# waveshaper.net
KiCad netlist of a schematic drawn in EAGLE
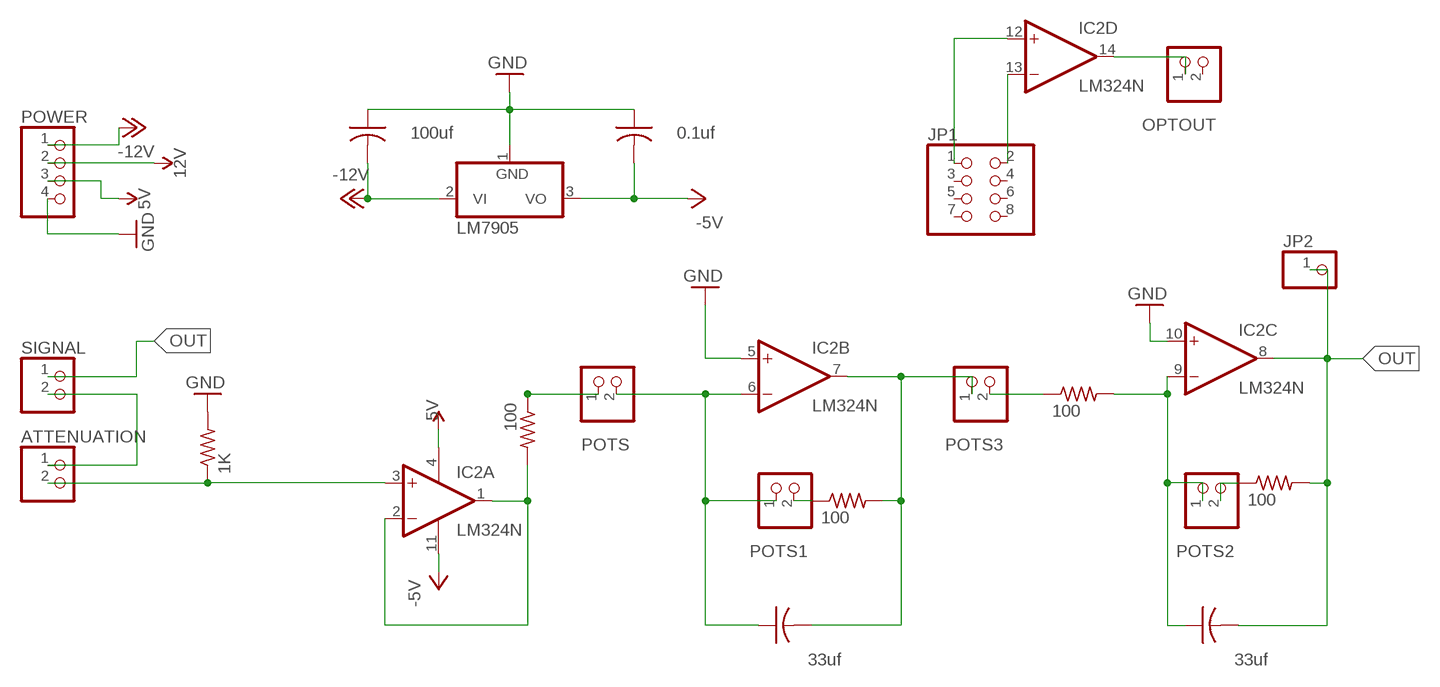
[diagram p0: schematic, sheet 1]

(export (version "E")
  (design (tool "Eeschema 10.0.6"))
  (components
    (comp (ref "ATTENUATION")
      (value "PINHD-1X2")
      (footprint "eagle-import:1X02")
      (libsource (lib "eagle-import") (part "PINHD-1X2"))
    )
    (comp (ref "C1")
      (value "100uf")
      (footprint "eagle-import:C025-024X044")
      (libsource (lib "eagle-import") (part "C-US025-024X044"))
    )
    (comp (ref "C2")
      (value "0.1uf")
      (footprint "eagle-import:C025-024X044")
      (libsource (lib "eagle-import") (part "C-US025-024X044"))
    )
    (comp (ref "C3")
      (value "33uf")
      (footprint "eagle-import:C025-024X044")
      (libsource (lib "eagle-import") (part "C-US025-024X044"))
    )
    (comp (ref "C4")
      (value "33uf")
      (footprint "eagle-import:C025-024X044")
      (libsource (lib "eagle-import") (part "C-US025-024X044"))
    )
    (comp (ref "IC2")
      (value "LM324N")
      (footprint "eagle-import:DIL14")
      (libsource (lib "eagle-import") (part "LM324N"))
    )
    (comp (ref "JP1")
      (value "PINHD-2X4")
      (footprint "eagle-import:2X04")
      (libsource (lib "eagle-import") (part "PINHD-2X4"))
    )
    (comp (ref "JP2")
      (value "PINHD-1X1")
      (footprint "eagle-import:1X01")
      (libsource (lib "eagle-import") (part "PINHD-1X1"))
    )
    (comp (ref "LM7905")
      (value "7905T")
      (footprint "eagle-import:TO220H")
      (libsource (lib "eagle-import") (part "79T05"))
    )
    (comp (ref "OPTOUT")
      (value "PINHD-1X2")
      (footprint "eagle-import:1X02")
      (libsource (lib "eagle-import") (part "PINHD-1X2"))
    )
    (comp (ref "POTS")
      (value "PINHD-1X2")
      (footprint "eagle-import:1X02")
      (libsource (lib "eagle-import") (part "PINHD-1X2"))
    )
    (comp (ref "POTS1")
      (value "PINHD-1X2")
      (footprint "eagle-import:1X02")
      (libsource (lib "eagle-import") (part "PINHD-1X2"))
    )
    (comp (ref "POTS2")
      (value "PINHD-1X2")
      (footprint "eagle-import:1X02")
      (libsource (lib "eagle-import") (part "PINHD-1X2"))
    )
    (comp (ref "POTS3")
      (value "PINHD-1X2")
      (footprint "eagle-import:1X02")
      (libsource (lib "eagle-import") (part "PINHD-1X2"))
    )
    (comp (ref "POWER")
      (value "PINHD-1X4")
      (footprint "eagle-import:1X04")
      (libsource (lib "eagle-import") (part "PINHD-1X4"))
    )
    (comp (ref "R1")
      (value "1K")
      (footprint "eagle-import:0207_12")
      (libsource (lib "eagle-import") (part "R-US_0207/12"))
    )
    (comp (ref "R2")
      (value "100")
      (footprint "eagle-import:0207_12")
      (libsource (lib "eagle-import") (part "R-US_0207/12"))
    )
    (comp (ref "R3")
      (value "100")
      (footprint "eagle-import:0207_12")
      (libsource (lib "eagle-import") (part "R-US_0207/12"))
    )
    (comp (ref "R4")
      (value "100")
      (footprint "eagle-import:0207_12")
      (libsource (lib "eagle-import") (part "R-US_0207/12"))
    )
    (comp (ref "R5")
      (value "100")
      (footprint "eagle-import:0207_12")
      (libsource (lib "eagle-import") (part "R-US_0207/12"))
    )
    (comp (ref "SIGNAL")
      (value "PINHD-1X2")
      (footprint "eagle-import:1X02")
      (libsource (lib "eagle-import") (part "PINHD-1X2"))
    )
  )
  (nets
    (net (code "1") (name "-5V") (class "Default")
      (node (ref "C2") (pin "2") (pinfunction "2_2") (pintype "passive"))
      (node (ref "IC2") (pin "11") (pinfunction "V-_11") (pintype "power_in"))
      (node (ref "LM7905") (pin "3") (pinfunction "VO_3") (pintype "passive"))
    )
    (net (code "2") (name "-12V") (class "Default")
      (node (ref "C1") (pin "2") (pinfunction "2_2") (pintype "passive"))
      (node (ref "LM7905") (pin "2") (pinfunction "VI_2") (pintype "input"))
      (node (ref "POWER") (pin "1") (pinfunction "1_1") (pintype "passive"))
    )
    (net (code "3") (name "5V") (class "Default")
      (node (ref "IC2") (pin "4") (pinfunction "V+_4") (pintype "power_in"))
      (node (ref "POWER") (pin "3") (pinfunction "3_3") (pintype "passive"))
    )
    (net (code "4") (name "12V") (class "Default")
      (node (ref "POWER") (pin "2") (pinfunction "2_2") (pintype "passive"))
    )
    (net (code "5") (name "GND") (class "Default")
      (node (ref "C1") (pin "1") (pinfunction "1_1") (pintype "passive"))
      (node (ref "C2") (pin "1") (pinfunction "1_1") (pintype "passive"))
      (node (ref "IC2") (pin "10") (pinfunction "+IN_10") (pintype "input"))
      (node (ref "IC2") (pin "5") (pinfunction "+IN_5") (pintype "input"))
      (node (ref "LM7905") (pin "1") (pinfunction "GND_1") (pintype "passive"))
      (node (ref "POWER") (pin "4") (pinfunction "4_4") (pintype "passive"))
      (node (ref "R1") (pin "2") (pinfunction "2_2") (pintype "passive"))
    )
    (net (code "6") (name "Net-(ATTENUATION-Pad1)") (class "Default")
      (node (ref "ATTENUATION") (pin "1") (pinfunction "1_1") (pintype "passive"))
      (node (ref "SIGNAL") (pin "2") (pinfunction "2_2") (pintype "passive"))
    )
    (net (code "7") (name "Net-(IC2A-+IN)") (class "Default")
      (node (ref "ATTENUATION") (pin "2") (pinfunction "2_2") (pintype "passive"))
      (node (ref "IC2") (pin "3") (pinfunction "+IN_3") (pintype "input"))
      (node (ref "R1") (pin "1") (pinfunction "1_1") (pintype "passive"))
    )
    (net (code "8") (name "Net-(IC2A--IN)") (class "Default")
      (node (ref "IC2") (pin "1") (pinfunction "OUT_1") (pintype "output"))
      (node (ref "IC2") (pin "2") (pinfunction "-IN_2") (pintype "input"))
      (node (ref "R2") (pin "2") (pinfunction "2_2") (pintype "passive"))
    )
    (net (code "9") (name "Net-(IC2B--IN)") (class "Default")
      (node (ref "C3") (pin "1") (pinfunction "1_1") (pintype "passive"))
      (node (ref "IC2") (pin "6") (pinfunction "-IN_6") (pintype "input"))
      (node (ref "POTS") (pin "2") (pinfunction "2_2") (pintype "passive"))
      (node (ref "POTS1") (pin "1") (pinfunction "1_1") (pintype "passive"))
    )
    (net (code "10") (name "Net-(IC2B-OUT)") (class "Default")
      (node (ref "C3") (pin "2") (pinfunction "2_2") (pintype "passive"))
      (node (ref "IC2") (pin "7") (pinfunction "OUT_7") (pintype "output"))
      (node (ref "POTS3") (pin "1") (pinfunction "1_1") (pintype "passive"))
      (node (ref "R3") (pin "2") (pinfunction "2_2") (pintype "passive"))
    )
    (net (code "11") (name "Net-(IC2C--IN)") (class "Default")
      (node (ref "C4") (pin "1") (pinfunction "1_1") (pintype "passive"))
      (node (ref "IC2") (pin "9") (pinfunction "-IN_9") (pintype "input"))
      (node (ref "POTS2") (pin "1") (pinfunction "1_1") (pintype "passive"))
      (node (ref "R5") (pin "2") (pinfunction "2_2") (pintype "passive"))
    )
    (net (code "12") (name "Net-(IC2D-+IN)") (class "Default")
      (node (ref "IC2") (pin "12") (pinfunction "+IN_12") (pintype "input"))
      (node (ref "JP1") (pin "1") (pinfunction "1_1") (pintype "passive"))
    )
    (net (code "13") (name "Net-(IC2D--IN)") (class "Default")
      (node (ref "IC2") (pin "13") (pinfunction "-IN_13") (pintype "input"))
      (node (ref "JP1") (pin "2") (pinfunction "2_2") (pintype "passive"))
    )
    (net (code "14") (name "Net-(IC2D-OUT)") (class "Default")
      (node (ref "IC2") (pin "14") (pinfunction "OUT_14") (pintype "output"))
      (node (ref "OPTOUT") (pin "1") (pinfunction "1_1") (pintype "passive"))
    )
    (net (code "15") (name "Net-(POTS-Pad1)") (class "Default")
      (node (ref "POTS") (pin "1") (pinfunction "1_1") (pintype "passive"))
      (node (ref "R2") (pin "1") (pinfunction "1_1") (pintype "passive"))
    )
    (net (code "16") (name "Net-(POTS1-Pad2)") (class "Default")
      (node (ref "POTS1") (pin "2") (pinfunction "2_2") (pintype "passive"))
      (node (ref "R3") (pin "1") (pinfunction "1_1") (pintype "passive"))
    )
    (net (code "17") (name "Net-(POTS2-Pad2)") (class "Default")
      (node (ref "POTS2") (pin "2") (pinfunction "2_2") (pintype "passive"))
      (node (ref "R4") (pin "1") (pinfunction "1_1") (pintype "passive"))
    )
    (net (code "18") (name "Net-(POTS3-Pad2)") (class "Default")
      (node (ref "POTS3") (pin "2") (pinfunction "2_2") (pintype "passive"))
      (node (ref "R5") (pin "1") (pinfunction "1_1") (pintype "passive"))
    )
    (net (code "19") (name "OUT") (class "Default")
      (node (ref "C4") (pin "2") (pinfunction "2_2") (pintype "passive"))
      (node (ref "IC2") (pin "8") (pinfunction "OUT_8") (pintype "output"))
      (node (ref "JP2") (pin "1") (pinfunction "1_1") (pintype "passive"))
      (node (ref "R4") (pin "2") (pinfunction "2_2") (pintype "passive"))
      (node (ref "SIGNAL") (pin "1") (pinfunction "1_1") (pintype "passive"))
    )
    (net (code "20") (name "unconnected-(JP1-Pad3)") (class "Default")
      (node (ref "JP1") (pin "3") (pinfunction "3_3") (pintype "passive"))
    )
    (net (code "21") (name "unconnected-(JP1-Pad4)") (class "Default")
      (node (ref "JP1") (pin "4") (pinfunction "4_4") (pintype "passive"))
    )
    (net (code "22") (name "unconnected-(JP1-Pad5)") (class "Default")
      (node (ref "JP1") (pin "5") (pinfunction "5_5") (pintype "passive"))
    )
    (net (code "23") (name "unconnected-(JP1-Pad6)") (class "Default")
      (node (ref "JP1") (pin "6") (pinfunction "6_6") (pintype "passive"))
    )
    (net (code "24") (name "unconnected-(JP1-Pad7)") (class "Default")
      (node (ref "JP1") (pin "7") (pinfunction "7_7") (pintype "passive"))
    )
    (net (code "25") (name "unconnected-(JP1-Pad8)") (class "Default")
      (node (ref "JP1") (pin "8") (pinfunction "8_8") (pintype "passive"))
    )
    (net (code "26") (name "unconnected-(OPTOUT-Pad2)") (class "Default")
      (node (ref "OPTOUT") (pin "2") (pinfunction "2_2") (pintype "passive"))
    )
  )
)
